# ventmon_t0_5i.net
KiCad netlist of a schematic drawn in EAGLE
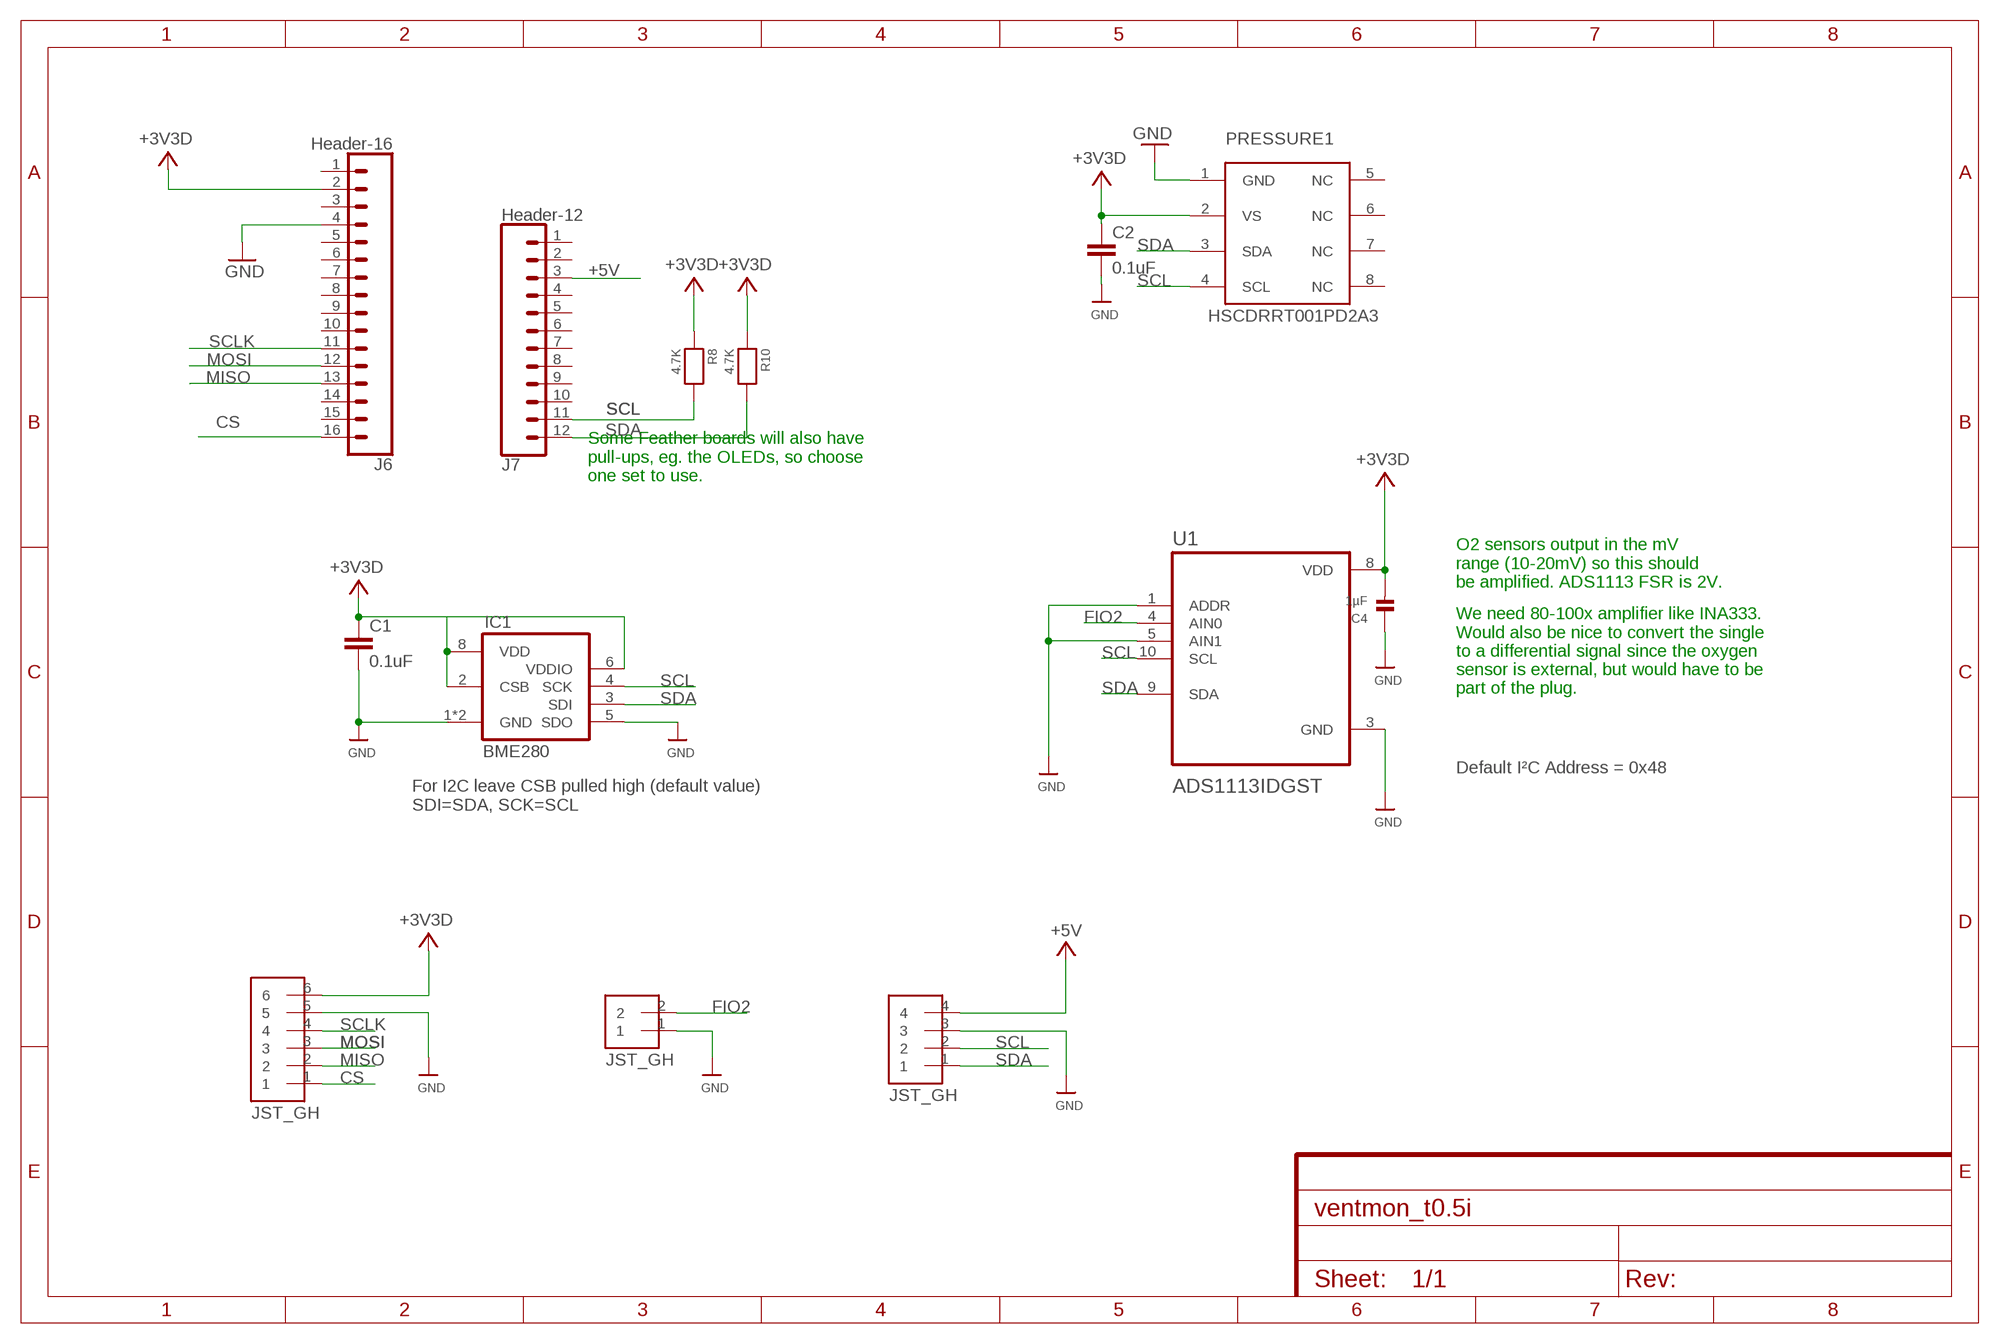
[diagram p0: schematic, sheet 1]

(export (version "E")
  (design (tool "Eeschema 10.0.6"))
  (components
    (comp (ref "C1")
      (value "0.1uF")
      (footprint "eagle-import:0603")
      (libsource (lib "eagle-import") (part "0.1UF-0603-25V-5%"))
    )
    (comp (ref "C2")
      (value "0.1uF")
      (footprint "eagle-import:0603")
      (libsource (lib "eagle-import") (part "0.1UF-0603-25V-5%"))
    )
    (comp (ref "C4")
      (value "1µF")
      (footprint "eagle-import:0603")
      (libsource (lib "eagle-import") (part "CAP_CERAMIC0603"))
    )
    (comp (ref "IC1")
      (value "BME280")
      (footprint "eagle-import:BME280")
      (libsource (lib "eagle-import") (part "BME280"))
    )
    (comp (ref "J6")
      (value "Header-16")
      (footprint "eagle-import:1X16")
      (libsource (lib "eagle-import") (part "CONN_16"))
    )
    (comp (ref "J7")
      (value "Header-12")
      (footprint "eagle-import:1X12")
      (libsource (lib "eagle-import") (part "CONN_12"))
    )
    (comp (ref "PRESSURE1")
      (value "HSCDRRT001PD2A3")
      (footprint "eagle-import:DIP1330W46P254L1000H616Q8B")
      (libsource (lib "eagle-import") (part "HSCDRRT001PD2A3"))
    )
    (comp (ref "R8")
      (value "4.7K")
      (footprint "eagle-import:0603")
      (libsource (lib "eagle-import") (part "RESISTOR0603"))
    )
    (comp (ref "R10")
      (value "4.7K")
      (footprint "eagle-import:0603")
      (libsource (lib "eagle-import") (part "RESISTOR0603"))
    )
    (comp (ref "U$5")
      (value "JST_GH_4")
      (footprint "eagle-import:JST_GH_4")
      (libsource (lib "eagle-import") (part "JST_GH_4"))
    )
    (comp (ref "U$6")
      (value "JST_GH_6")
      (footprint "eagle-import:JST_GH_6")
      (libsource (lib "eagle-import") (part "JST_GH_6"))
    )
    (comp (ref "U$12")
      (value "JST_GH_2")
      (footprint "eagle-import:JST_GH_2")
      (libsource (lib "eagle-import") (part "JST_GH_2"))
    )
    (comp (ref "U1")
      (value "ADS1113IDGST")
      (footprint "eagle-import:SOP50P490X110-10N")
      (fields (field (name "DIGI-KEY_PART_NUMBER") "296-24930-2-ND") (field (name "MF") "Texas Instruments"))
      (libsource (lib "eagle-import") (part "ADS1113IDGST"))
    )
  )
  (nets
    (net (code "1") (name "+3V3D") (class "Default")
      (node (ref "C1") (pin "1") (pinfunction "1_1") (pintype "passive"))
      (node (ref "C2") (pin "1") (pinfunction "1_1") (pintype "passive"))
      (node (ref "C4") (pin "2") (pinfunction "P$2_2") (pintype "passive"))
      (node (ref "IC1") (pin "2") (pinfunction "CSB_2") (pintype "input"))
      (node (ref "IC1") (pin "6") (pinfunction "VDDIO_6") (pintype "power_in"))
      (node (ref "IC1") (pin "8") (pinfunction "VDD_8") (pintype "power_in"))
      (node (ref "J6") (pin "2") (pinfunction "2_2") (pintype "passive"))
      (node (ref "PRESSURE1") (pin "2") (pinfunction "VS_2") (pintype "bidirectional"))
      (node (ref "R10") (pin "1") (pinfunction "1_1") (pintype "passive"))
      (node (ref "R8") (pin "1") (pinfunction "1_1") (pintype "passive"))
      (node (ref "U$6") (pin "6") (pinfunction "6_6") (pintype "bidirectional"))
      (node (ref "U1") (pin "8") (pinfunction "VDD_8") (pintype "power_in"))
    )
    (net (code "2") (name "+5V") (class "Default")
      (node (ref "J7") (pin "3") (pinfunction "3_3") (pintype "passive"))
      (node (ref "U$5") (pin "4") (pinfunction "4_4") (pintype "bidirectional"))
    )
    (net (code "3") (name "/CS") (class "Default")
      (node (ref "J6") (pin "16") (pinfunction "16_16") (pintype "passive"))
      (node (ref "U$6") (pin "1") (pinfunction "1_1") (pintype "bidirectional"))
    )
    (net (code "4") (name "/FIO2") (class "Default")
      (node (ref "U$12") (pin "2") (pinfunction "2_2") (pintype "bidirectional"))
      (node (ref "U1") (pin "4") (pinfunction "AIN0_4") (pintype "input"))
    )
    (net (code "5") (name "/MISO") (class "Default")
      (node (ref "J6") (pin "13") (pinfunction "13_13") (pintype "passive"))
      (node (ref "U$6") (pin "2") (pinfunction "2_2") (pintype "bidirectional"))
    )
    (net (code "6") (name "/MOSI") (class "Default")
      (node (ref "J6") (pin "12") (pinfunction "12_12") (pintype "passive"))
      (node (ref "U$6") (pin "3") (pinfunction "3_3") (pintype "bidirectional"))
    )
    (net (code "7") (name "/SCL") (class "Default")
      (node (ref "IC1") (pin "4") (pinfunction "SCK_4") (pintype "bidirectional"))
      (node (ref "J7") (pin "11") (pinfunction "11_11") (pintype "passive"))
      (node (ref "PRESSURE1") (pin "4") (pinfunction "SCL_4") (pintype "bidirectional"))
      (node (ref "R8") (pin "2") (pinfunction "2_2") (pintype "passive"))
      (node (ref "U$5") (pin "2") (pinfunction "2_2") (pintype "bidirectional"))
      (node (ref "U1") (pin "10") (pinfunction "SCL_10") (pintype "input"))
    )
    (net (code "8") (name "/SCLK") (class "Default")
      (node (ref "J6") (pin "11") (pinfunction "11_11") (pintype "passive"))
      (node (ref "U$6") (pin "4") (pinfunction "4_4") (pintype "bidirectional"))
    )
    (net (code "9") (name "/SDA") (class "Default")
      (node (ref "IC1") (pin "3") (pinfunction "SDI_3") (pintype "bidirectional"))
      (node (ref "J7") (pin "12") (pinfunction "12_12") (pintype "passive"))
      (node (ref "PRESSURE1") (pin "3") (pinfunction "SDA_3") (pintype "bidirectional"))
      (node (ref "R10") (pin "2") (pinfunction "2_2") (pintype "passive"))
      (node (ref "U$5") (pin "1") (pinfunction "1_1") (pintype "bidirectional"))
      (node (ref "U1") (pin "9") (pinfunction "SDA_9") (pintype "bidirectional"))
    )
    (net (code "10") (name "GND") (class "Default")
      (node (ref "C1") (pin "2") (pinfunction "2_2") (pintype "passive"))
      (node (ref "C2") (pin "2") (pinfunction "2_2") (pintype "passive"))
      (node (ref "C4") (pin "1") (pinfunction "P$1_1") (pintype "passive"))
      (node (ref "IC1") (pin "1") (pinfunction "GND_1") (pintype "power_in"))
      (node (ref "IC1") (pin "5") (pinfunction "SDO_5") (pintype "input"))
      (node (ref "IC1") (pin "7") (pinfunction "GND_7") (pintype "power_in"))
      (node (ref "J6") (pin "4") (pinfunction "4_4") (pintype "passive"))
      (node (ref "PRESSURE1") (pin "1") (pinfunction "GND_1") (pintype "bidirectional"))
      (node (ref "U$12") (pin "1") (pinfunction "1_1") (pintype "bidirectional"))
      (node (ref "U$5") (pin "3") (pinfunction "3_3") (pintype "bidirectional"))
      (node (ref "U$6") (pin "5") (pinfunction "5_5") (pintype "bidirectional"))
      (node (ref "U1") (pin "1") (pinfunction "ADDR_1") (pintype "input"))
      (node (ref "U1") (pin "3") (pinfunction "GND_3") (pintype "power_in"))
      (node (ref "U1") (pin "5") (pinfunction "AIN1_5") (pintype "input"))
    )
    (net (code "11") (name "unconnected-(J6-Pad1)") (class "Default")
      (node (ref "J6") (pin "1") (pinfunction "1_1") (pintype "passive"))
    )
    (net (code "12") (name "unconnected-(J6-Pad3)") (class "Default")
      (node (ref "J6") (pin "3") (pinfunction "3_3") (pintype "passive"))
    )
    (net (code "13") (name "unconnected-(J6-Pad5)") (class "Default")
      (node (ref "J6") (pin "5") (pinfunction "5_5") (pintype "passive"))
    )
    (net (code "14") (name "unconnected-(J6-Pad6)") (class "Default")
      (node (ref "J6") (pin "6") (pinfunction "6_6") (pintype "passive"))
    )
    (net (code "15") (name "unconnected-(J6-Pad7)") (class "Default")
      (node (ref "J6") (pin "7") (pinfunction "7_7") (pintype "passive"))
    )
    (net (code "16") (name "unconnected-(J6-Pad8)") (class "Default")
      (node (ref "J6") (pin "8") (pinfunction "8_8") (pintype "passive"))
    )
    (net (code "17") (name "unconnected-(J6-Pad9)") (class "Default")
      (node (ref "J6") (pin "9") (pinfunction "9_9") (pintype "passive"))
    )
    (net (code "18") (name "unconnected-(J6-Pad10)") (class "Default")
      (node (ref "J6") (pin "10") (pinfunction "10_10") (pintype "passive"))
    )
    (net (code "19") (name "unconnected-(J6-Pad14)") (class "Default")
      (node (ref "J6") (pin "14") (pinfunction "14_14") (pintype "passive"))
    )
    (net (code "20") (name "unconnected-(J6-Pad15)") (class "Default")
      (node (ref "J6") (pin "15") (pinfunction "15_15") (pintype "passive"))
    )
    (net (code "21") (name "unconnected-(J7-Pad1)") (class "Default")
      (node (ref "J7") (pin "1") (pinfunction "1_1") (pintype "passive"))
    )
    (net (code "22") (name "unconnected-(J7-Pad2)") (class "Default")
      (node (ref "J7") (pin "2") (pinfunction "2_2") (pintype "passive"))
    )
    (net (code "23") (name "unconnected-(J7-Pad4)") (class "Default")
      (node (ref "J7") (pin "4") (pinfunction "4_4") (pintype "passive"))
    )
    (net (code "24") (name "unconnected-(J7-Pad5)") (class "Default")
      (node (ref "J7") (pin "5") (pinfunction "5_5") (pintype "passive"))
    )
    (net (code "25") (name "unconnected-(J7-Pad6)") (class "Default")
      (node (ref "J7") (pin "6") (pinfunction "6_6") (pintype "passive"))
    )
    (net (code "26") (name "unconnected-(J7-Pad7)") (class "Default")
      (node (ref "J7") (pin "7") (pinfunction "7_7") (pintype "passive"))
    )
    (net (code "27") (name "unconnected-(J7-Pad8)") (class "Default")
      (node (ref "J7") (pin "8") (pinfunction "8_8") (pintype "passive"))
    )
    (net (code "28") (name "unconnected-(J7-Pad9)") (class "Default")
      (node (ref "J7") (pin "9") (pinfunction "9_9") (pintype "passive"))
    )
    (net (code "29") (name "unconnected-(J7-Pad10)") (class "Default")
      (node (ref "J7") (pin "10") (pinfunction "10_10") (pintype "passive"))
    )
    (net (code "30") (name "unconnected-(PRESSURE1-NC-Pad5)") (class "Default")
      (node (ref "PRESSURE1") (pin "5") (pinfunction "NC_5") (pintype "bidirectional"))
    )
    (net (code "31") (name "unconnected-(PRESSURE1-NC-Pad6)") (class "Default")
      (node (ref "PRESSURE1") (pin "6") (pinfunction "NC_6") (pintype "bidirectional"))
    )
    (net (code "32") (name "unconnected-(PRESSURE1-NC-Pad7)") (class "Default")
      (node (ref "PRESSURE1") (pin "7") (pinfunction "NC_7") (pintype "bidirectional"))
    )
    (net (code "33") (name "unconnected-(PRESSURE1-NC-Pad8)") (class "Default")
      (node (ref "PRESSURE1") (pin "8") (pinfunction "NC_8") (pintype "bidirectional"))
    )
  )
)
